# ComboSensorBreakout.net
KiCad netlist of a schematic drawn in EAGLE
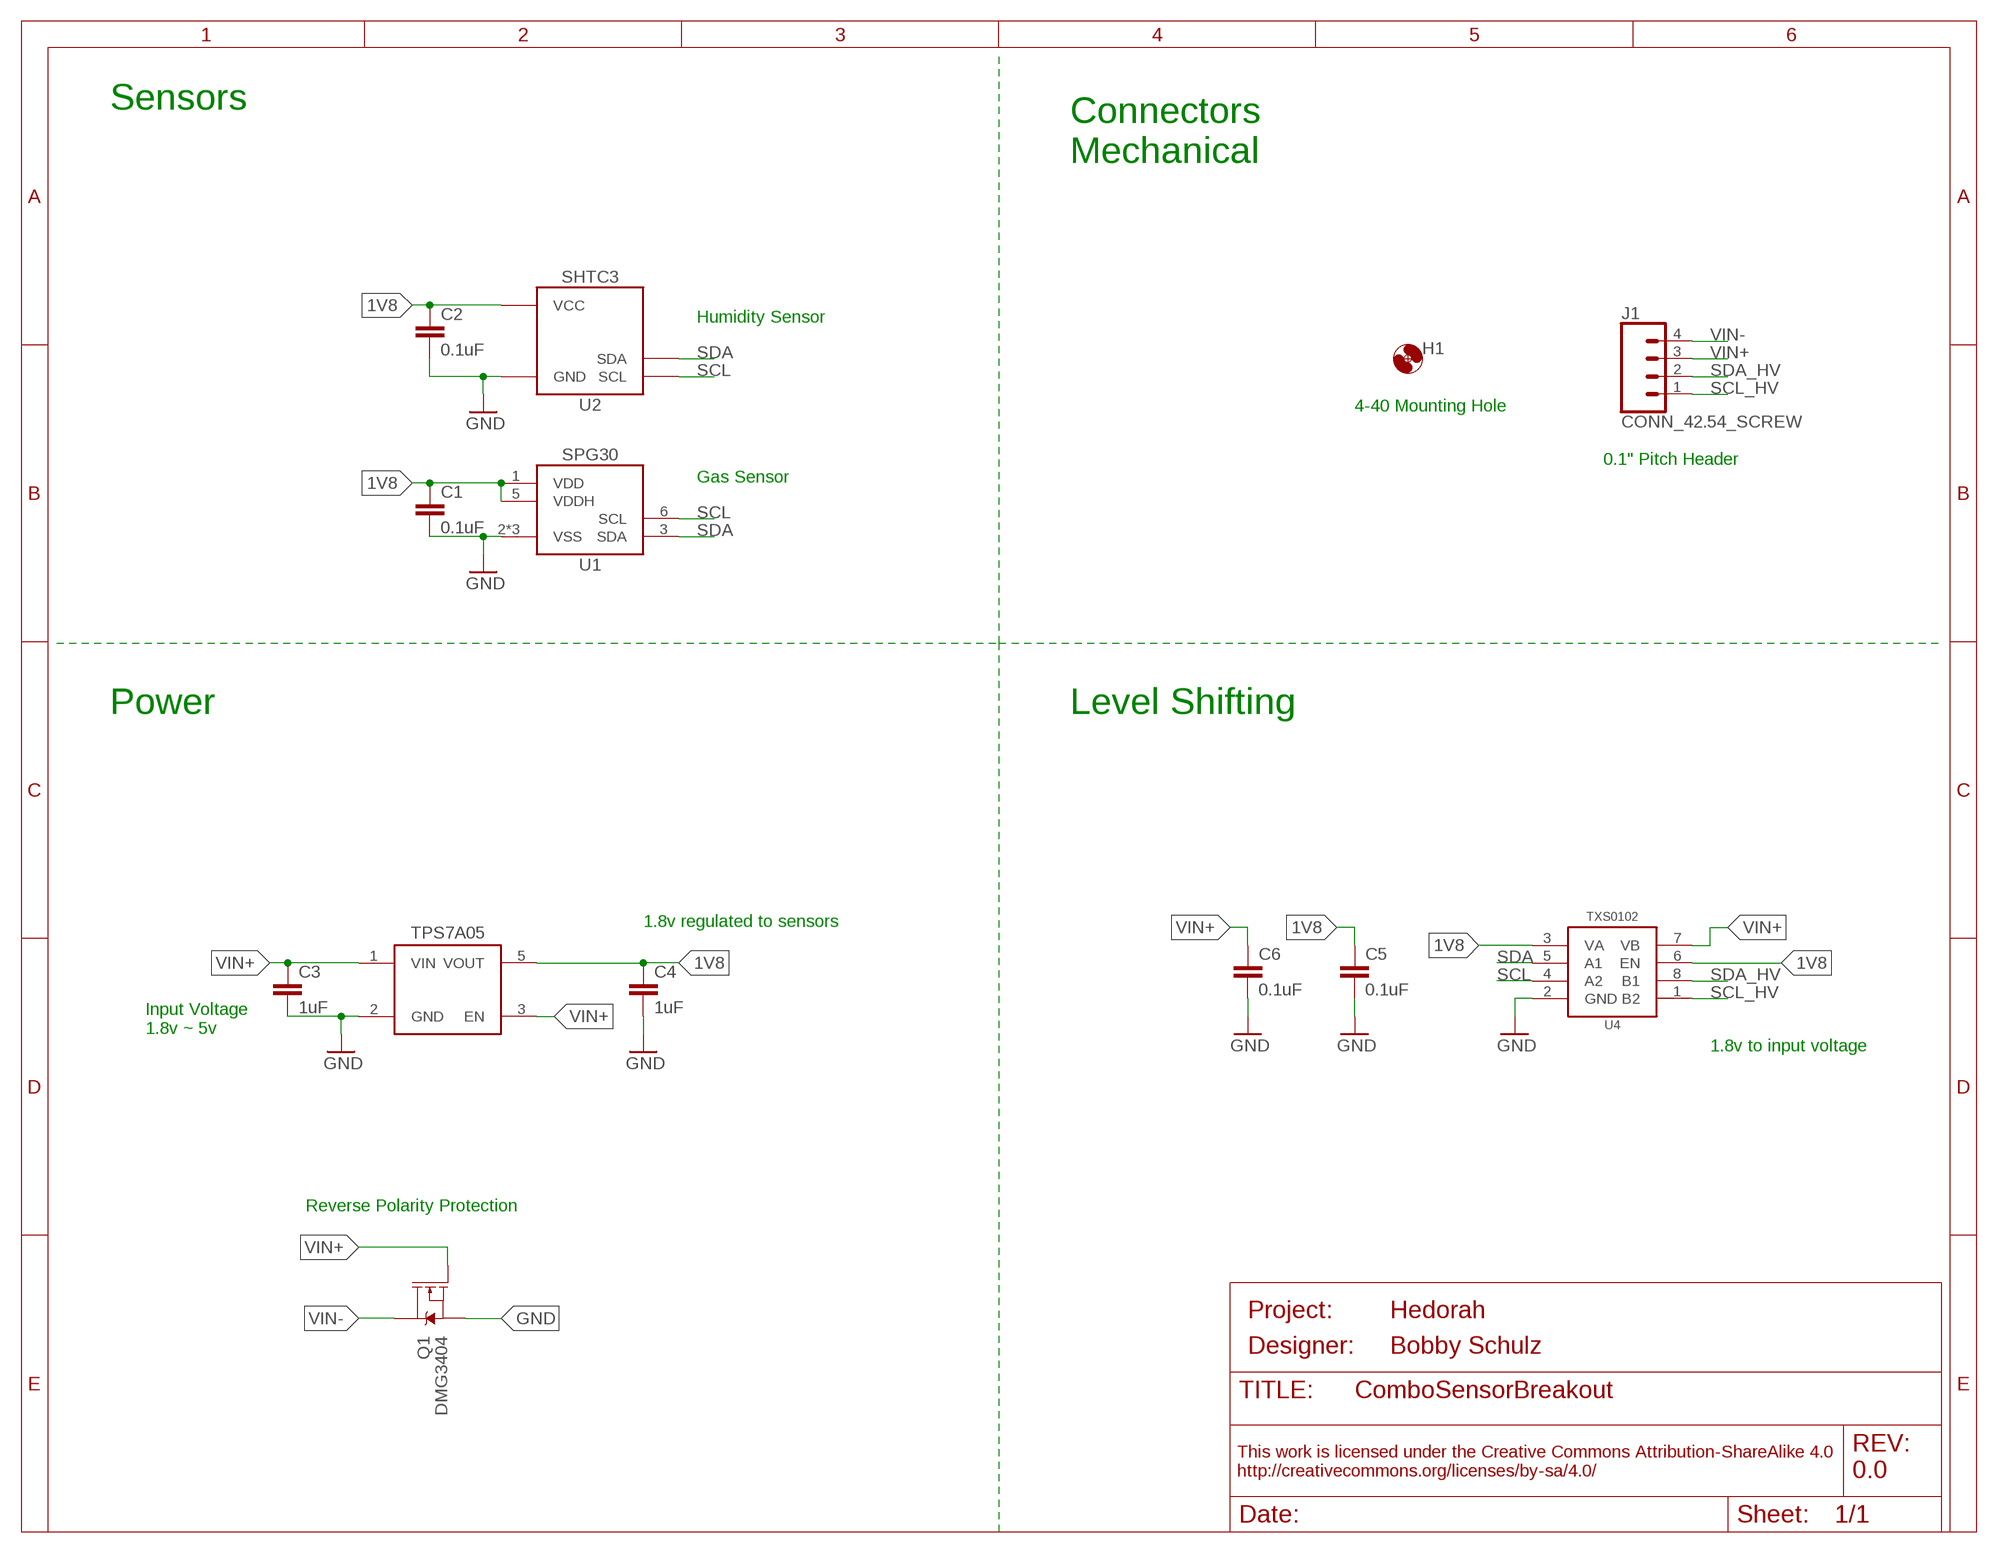
[diagram p0: schematic, sheet 1]

(export (version "E")
  (design (tool "Eeschema 10.0.6"))
  (components
    (comp (ref "C1")
      (value "0.1uF")
      (footprint "eagle-import:C0603")
      (fields (field (name "MF") "Murata") (field (name "MPN") "GCM188R71E104KA57D"))
      (libsource (lib "eagle-import") (part "C-EUC06030.1UF"))
    )
    (comp (ref "C2")
      (value "0.1uF")
      (footprint "eagle-import:C0603")
      (fields (field (name "MF") "Murata") (field (name "MPN") "GCM188R71E104KA57D"))
      (libsource (lib "eagle-import") (part "C-EUC06030.1UF"))
    )
    (comp (ref "C3")
      (value "1uF")
      (footprint "eagle-import:C0603")
      (fields (field (name "MF") "Murata") (field (name "MPN") "GRM188R61C105KA12D"))
      (libsource (lib "eagle-import") (part "C-EUC06031UF"))
    )
    (comp (ref "C4")
      (value "1uF")
      (footprint "eagle-import:C0603")
      (fields (field (name "MF") "Murata") (field (name "MPN") "GRM188R61C105KA12D"))
      (libsource (lib "eagle-import") (part "C-EUC06031UF"))
    )
    (comp (ref "C5")
      (value "0.1uF")
      (footprint "eagle-import:C0603")
      (fields (field (name "MF") "Murata") (field (name "MPN") "GCM188R71E104KA57D"))
      (libsource (lib "eagle-import") (part "C-EUC06030.1UF"))
    )
    (comp (ref "C6")
      (value "0.1uF")
      (footprint "eagle-import:C0603")
      (fields (field (name "MF") "Murata") (field (name "MPN") "GCM188R71E104KA57D"))
      (libsource (lib "eagle-import") (part "C-EUC06030.1UF"))
    )
    (comp (ref "H1")
      (value "MOUNTING_HOLE4_NP")
      (footprint "eagle-import:4_40")
      (fields (field (name "MPN") "DNP"))
      (libsource (lib "eagle-import") (part "MOUNTING_HOLE4_NP"))
    )
    (comp (ref "J1")
      (value "CONN_42.54_SCREW")
      (footprint "eagle-import:1X04_SCREW")
      (fields (field (name "MF") "On Shore") (field (name "MPN") "OSTVN04A150"))
      (libsource (lib "eagle-import") (part "CONN_42.54_SCREW"))
    )
    (comp (ref "Q1")
      (value "DMG3404")
      (footprint "eagle-import:SOT23-3")
      (fields (field (name "MF") "Diodes Incorporated") (field (name "MPN") "DMG3404L-7"))
      (libsource (lib "eagle-import") (part "MOSFET-NCH-DMG3404L"))
    )
    (comp (ref "U1")
      (value "SPG30")
      (footprint "eagle-import:DFN_6_2.5X2.5")
      (fields (field (name "MF") "Sensirion") (field (name "MPN") "SGP30-2.5K"))
      (libsource (lib "eagle-import") (part "SPG30"))
    )
    (comp (ref "U2")
      (value "SHTC3DFN")
      (footprint "eagle-import:DFN_4_2X2")
      (fields (field (name "DISP") "SHTC3") (field (name "MF") "Sensirion") (field (name "MPN") "SHTC3"))
      (libsource (lib "eagle-import") (part "SHTCDFN3"))
    )
    (comp (ref "U3")
      (value "TPS7A0518DBV")
      (footprint "eagle-import:SOT23-5")
      (fields
        (field (name "MF") "TI")
        (field (name "MPN") "TPS7A0518PDBVR")
        (field (name "DIGIKEY") "296-50251-1-ND")
      )
      (libsource (lib "eagle-import") (part "TPS7A05DBV18"))
    )
    (comp (ref "U4")
      (value "TXS0102DCU")
      (footprint "eagle-import:DCU_(R-PDSO-G8)")
      (fields (field (name "MF") "TI") (field (name "MPN") "TXS0102DCUR"))
      (libsource (lib "eagle-import") (part "TXS0102DCU"))
    )
  )
  (nets
    (net (code "1") (name "/SCL") (class "Default")
      (node (ref "U1") (pin "6") (pinfunction "SCL_6") (pintype "input"))
      (node (ref "U2") (pin "2") (pinfunction "SCL_2") (pintype "input"))
      (node (ref "U4") (pin "4") (pinfunction "A2_4") (pintype "bidirectional"))
    )
    (net (code "2") (name "/SCL_HV") (class "Default")
      (node (ref "J1") (pin "1") (pinfunction "1_1") (pintype "passive"))
      (node (ref "U4") (pin "1") (pinfunction "B2_1") (pintype "bidirectional"))
    )
    (net (code "3") (name "/SDA") (class "Default")
      (node (ref "U1") (pin "3") (pinfunction "SDA_3") (pintype "bidirectional"))
      (node (ref "U2") (pin "3") (pinfunction "SDA_3") (pintype "bidirectional"))
      (node (ref "U4") (pin "5") (pinfunction "A1_5") (pintype "bidirectional"))
    )
    (net (code "4") (name "/SDA_HV") (class "Default")
      (node (ref "J1") (pin "2") (pinfunction "2_2") (pintype "passive"))
      (node (ref "U4") (pin "8") (pinfunction "B1_8") (pintype "bidirectional"))
    )
    (net (code "5") (name "1V8") (class "Default")
      (node (ref "C1") (pin "1") (pinfunction "1_1") (pintype "passive"))
      (node (ref "C2") (pin "1") (pinfunction "1_1") (pintype "passive"))
      (node (ref "C4") (pin "1") (pinfunction "1_1") (pintype "passive"))
      (node (ref "C5") (pin "1") (pinfunction "1_1") (pintype "passive"))
      (node (ref "U1") (pin "1") (pinfunction "VDD_1") (pintype "power_in"))
      (node (ref "U1") (pin "5") (pinfunction "VDDH_5") (pintype "power_in"))
      (node (ref "U2") (pin "1") (pinfunction "VCC_1") (pintype "power_in"))
      (node (ref "U3") (pin "5") (pinfunction "VOUT_5") (pintype "power_in"))
      (node (ref "U4") (pin "3") (pinfunction "VA_3") (pintype "power_in"))
      (node (ref "U4") (pin "6") (pinfunction "EN_6") (pintype "input"))
    )
    (net (code "6") (name "GND") (class "Default")
      (node (ref "C1") (pin "2") (pinfunction "2_2") (pintype "passive"))
      (node (ref "C2") (pin "2") (pinfunction "2_2") (pintype "passive"))
      (node (ref "C3") (pin "2") (pinfunction "2_2") (pintype "passive"))
      (node (ref "C4") (pin "2") (pinfunction "2_2") (pintype "passive"))
      (node (ref "C5") (pin "2") (pinfunction "2_2") (pintype "passive"))
      (node (ref "C6") (pin "2") (pinfunction "2_2") (pintype "passive"))
      (node (ref "Q1") (pin "2") (pinfunction "S_2") (pintype "bidirectional"))
      (node (ref "U1") (pin "2") (pinfunction "VSS_2") (pintype "power_in"))
      (node (ref "U1") (pin "4") (pinfunction "VSS_4") (pintype "power_in"))
      (node (ref "U1") (pin "EP") (pinfunction "VSS_EP") (pintype "power_in"))
      (node (ref "U2") (pin "4") (pinfunction "GND_4") (pintype "power_in"))
      (node (ref "U2") (pin "EP") (pinfunction "GND_EP") (pintype "power_in"))
      (node (ref "U3") (pin "2") (pinfunction "GND_2") (pintype "power_in"))
      (node (ref "U4") (pin "2") (pinfunction "GND_2") (pintype "power_in"))
    )
    (net (code "7") (name "VIN+") (class "Default")
      (node (ref "C3") (pin "1") (pinfunction "1_1") (pintype "passive"))
      (node (ref "C6") (pin "1") (pinfunction "1_1") (pintype "passive"))
      (node (ref "J1") (pin "3") (pinfunction "3_3") (pintype "passive"))
      (node (ref "Q1") (pin "1") (pinfunction "G_1") (pintype "bidirectional"))
      (node (ref "U3") (pin "1") (pinfunction "VIN_1") (pintype "power_in"))
      (node (ref "U3") (pin "3") (pinfunction "EN_3") (pintype "input"))
      (node (ref "U4") (pin "7") (pinfunction "VB_7") (pintype "power_in"))
    )
    (net (code "8") (name "VIN-") (class "Default")
      (node (ref "J1") (pin "4") (pinfunction "4_4") (pintype "passive"))
      (node (ref "Q1") (pin "3") (pinfunction "D_3") (pintype "bidirectional"))
    )
  )
)
